# MCU.net
KiCad netlist of a schematic drawn in Altium Designer
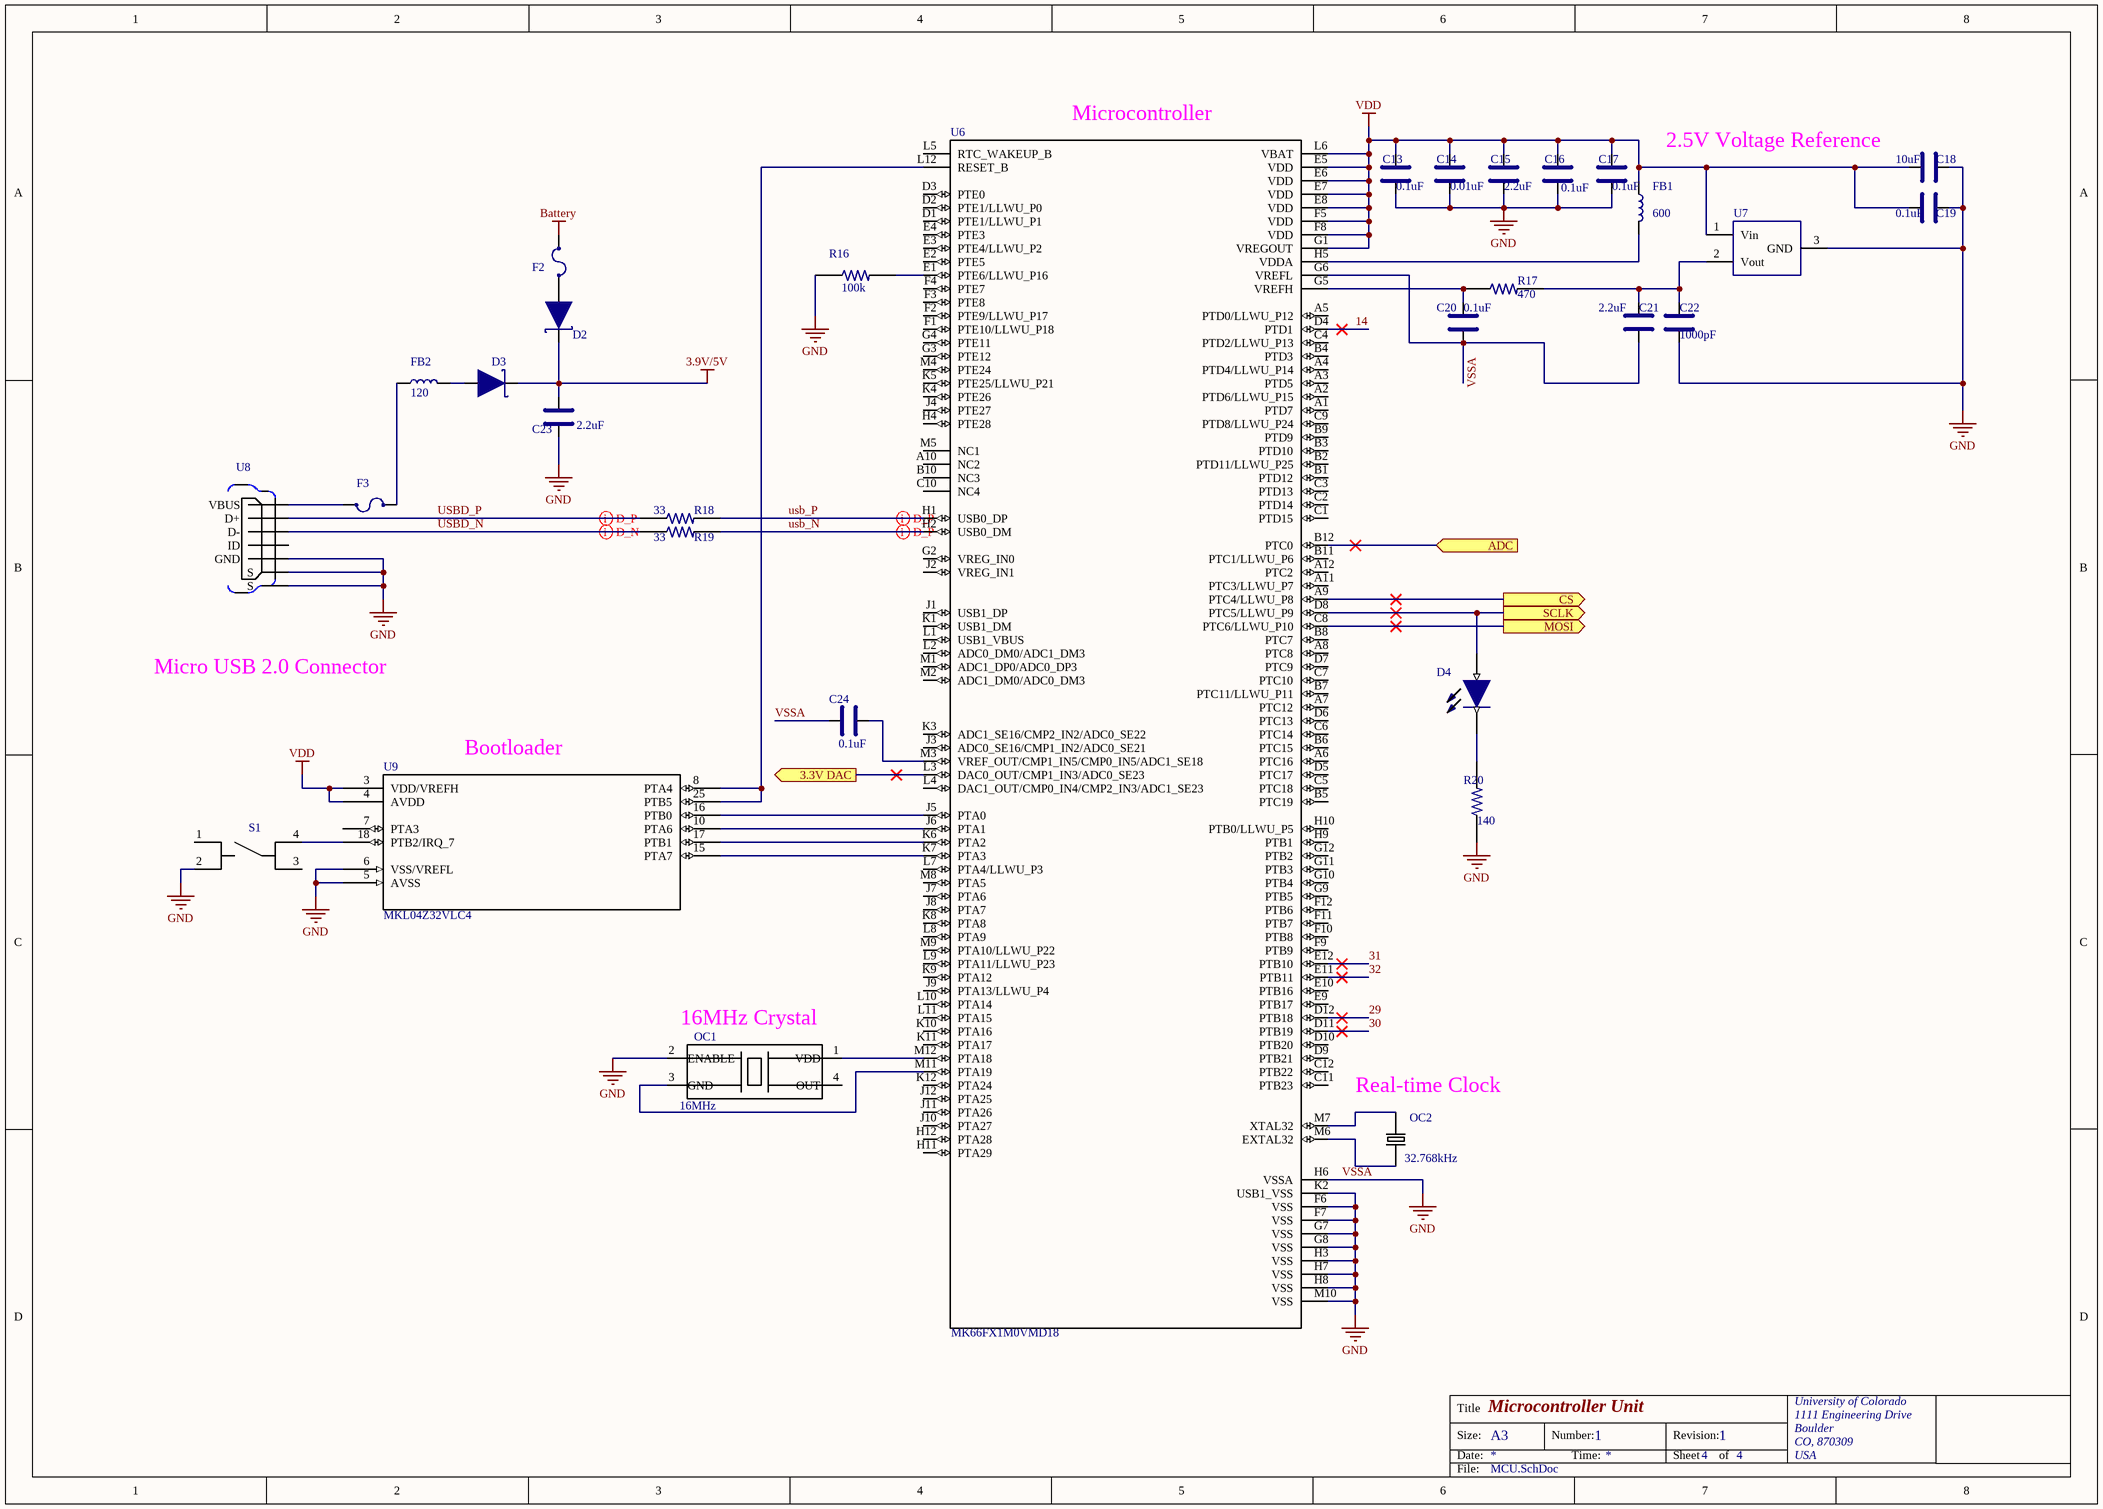
[diagram p0: MCU.SchDoc]

(export (version "E")
  (design (tool "Eeschema 10.0.6"))
  (components
    (comp (ref "C13")
      (value "0.1uF")
      (footprint "CL03A104KA3NNNC")
      (description "CAP CER 0.1UF 25V X5R 0201")
      (fields
        (field (name "MANUFACTURER") "Samsung")
        (field (name "MANUFACTURER PART NUMBER") "CL03A104KA3NNNC")
      )
      (libsource (lib "Sensing PEANO_Library") (part "CL03A104KA3NNNC"))
    )
    (comp (ref "C14")
      (value "0.01uF")
      (footprint "CL03B103KP3NNNC")
      (description "CAP CER 10000PF 10V X7R 0201")
      (fields
        (field (name "MANUFACTURER") "Samsung")
        (field (name "MANUFACTURER PART NUMBER") "CL03B103KP3NNNC")
      )
      (libsource (lib "Sensing PEANO_Library") (part "CL03B103KP3NNNC"))
    )
    (comp (ref "C15")
      (value "2.2uF")
      (footprint "CL03A225MP3CRNC")
      (description "CAP CER 2.2UF 10V X5R 0201")
      (fields
        (field (name "MANUFACTURER") "Samsung")
        (field (name "MANUFACTURER PART NUMBER") "CL03A225MP3CRNC")
      )
      (libsource (lib "Sensing PEANO_Library") (part "CL03A225MP3CRNC"))
    )
    (comp (ref "C16")
      (value "0.1uF")
      (footprint "CL03A104KA3NNNC")
      (description "CAP CER 0.1UF 25V X5R 0201")
      (fields
        (field (name "MANUFACTURER") "Samsung")
        (field (name "MANUFACTURER PART NUMBER") "CL03A104KA3NNNC")
      )
      (libsource (lib "Control_Board_Library") (part "CL03A104KA3NNNC"))
    )
    (comp (ref "C17")
      (value "0.1uF")
      (footprint "CL03A104KA3NNNC")
      (description "CAP CER 0.1UF 25V X5R 0201")
      (fields
        (field (name "MANUFACTURER") "Samsung")
        (field (name "MANUFACTURER PART NUMBER") "CL03A104KA3NNNC")
      )
      (libsource (lib "Sensing PEANO_Library") (part "CL03A104KA3NNNC"))
    )
    (comp (ref "C18")
      (value "10uF")
      (footprint "GRM155R60J106ME47D")
      (description "CAP CER 10UF 6.3V X5R 0402")
      (fields
        (field (name "MANUFACTURER") "Murata")
        (field (name "MANUFACTURER PART NUMBER") "GRM155R60J106ME47D")
      )
      (libsource (lib "Sensing PEANO_Library") (part "GRM155R60J106ME47D"))
    )
    (comp (ref "C19")
      (value "0.1uF")
      (footprint "CL03A104KA3NNNC")
      (description "CAP CER 0.1UF 25V X5R 0201")
      (fields
        (field (name "MANUFACTURER") "Samsung")
        (field (name "MANUFACTURER PART NUMBER") "CL03A104KA3NNNC")
      )
      (libsource (lib "Sensing PEANO_Library") (part "CL03A104KA3NNNC"))
    )
    (comp (ref "C20")
      (value "0.1uF")
      (footprint "CL03A104KA3NNNC")
      (description "CAP CER 0.1UF 25V X5R 0201")
      (fields
        (field (name "MANUFACTURER") "Samsung")
        (field (name "MANUFACTURER PART NUMBER") "CL03A104KA3NNNC")
      )
      (libsource (lib "Sensing PEANO_Library") (part "CL03A104KA3NNNC"))
    )
    (comp (ref "C21")
      (value "2.2uF")
      (footprint "CL03A225MP3CRNC")
      (description "CAP CER 2.2UF 10V X5R 0201")
      (fields
        (field (name "MANUFACTURER") "Samsung")
        (field (name "MANUFACTURER PART NUMBER") "CL03A225MP3CRNC")
      )
      (libsource (lib "Sensing PEANO_Library") (part "CL03A225MP3CRNC"))
    )
    (comp (ref "C22")
      (value "1000pF")
      (footprint "C0402C102K9RACTU")
      (description "CAP CER 1000PF 6.3V X7R 0402")
      (fields
        (field (name "MANUFACTURER") "Murata")
        (field (name "MANUFACTURER PART NUMBER") "GRM155R60J106ME47D")
      )
      (libsource (lib "Sensing PEANO_Library") (part "C0402C102K9RACTU"))
    )
    (comp (ref "C23")
      (value "2.2uF")
      (footprint "CL03A225MP3CRNC")
      (description "CAP CER 2.2UF 10V X5R 0201")
      (fields
        (field (name "MANUFACTURER") "Samsung")
        (field (name "MANUFACTURER PART NUMBER") "CL03A225MP3CRNC")
      )
      (libsource (lib "Sensing PEANO_Library") (part "CL03A225MP3CRNC"))
    )
    (comp (ref "C24")
      (value "0.1uF")
      (footprint "CL03A104KA3NNNC")
      (description "CAP CER 0.1UF 25V X5R 0201")
      (fields
        (field (name "MANUFACTURER") "Samsung")
        (field (name "MANUFACTURER PART NUMBER") "CL03A104KA3NNNC")
      )
      (libsource (lib "Sensing PEANO_Library") (part "CL03A104KA3NNNC"))
    )
    (comp (ref "D2")
      (value "LSM115JE3/TR13")
      (footprint "LSM115JE3/TR13")
      (description "DIODE SCHOTTKY 15V 1A DO214AC")
      (fields
        (field (name "MANUFACTURER") "Microsemi")
        (field (name "DIGIKEY PART NUMBER") "LSM115JE3/TR13CT-ND")
      )
      (libsource (lib "Sensing PEANO_Library") (part "LSM115JE3/TR13"))
    )
    (comp (ref "D3")
      (value "LSM115JE3/TR13")
      (footprint "LSM115JE3/TR13")
      (description "DIODE SCHOTTKY 15V 1A DO214AC")
      (fields
        (field (name "MANUFACTURER") "Microsemi")
        (field (name "DIGIKEY PART NUMBER") "LSM115JE3/TR13CT-ND")
      )
      (libsource (lib "Sensing PEANO_Library") (part "LSM115JE3/TR13"))
    )
    (comp (ref "D4")
      (value "SML-LXFM0603SUGCTR")
      (footprint "SML-LXFM0603SUGCTR")
      (description "LED GREEN CLEAR SMD")
      (fields
        (field (name "MANUFACTURER") "Lumex Opto/Components Inc.")
        (field (name "DIGIKEY PART NUMBER") "67-2320-1-ND")
      )
      (libsource (lib "Control_Board_Library") (part "SML-LXFM0603SUGCTR"))
    )
    (comp (ref "F2")
      (value "ERB-SD0R50U")
      (footprint "ERB-SD0R50U")
      (description "FUSE BOARD MNT 500MA 24VDC 0402")
      (fields (field (name "MANUFACTURER") "Panasonic") (field (name "DIGIKEY PART NUMBER") "P11361CT-ND"))
      (libsource (lib "Sensing PEANO_Library") (part "ERB-SD0R50U"))
    )
    (comp (ref "F3")
      (value "ERB-SD0R50U")
      (footprint "ERB-SD0R50U")
      (description "FUSE BOARD MNT 500MA 24VDC 0402")
      (fields (field (name "MANUFACTURER") "Panasonic") (field (name "DIGIKEY PART NUMBER") "P11361CT-ND"))
      (libsource (lib "Sensing PEANO_Library") (part "ERB-SD0R50U"))
    )
    (comp (ref "FB1")
      (value "600")
      (footprint "BLM15PX601SN1D")
      (description "FERRITE BEAD 600 OHM 0402 1LN")
      (fields
        (field (name "MANUFACTURER") "Murata")
        (field (name "MANUFACTURER PART NUMBER") "BLM15PX601SN1D")
      )
      (libsource (lib "Sensing PEANO_Library") (part "BLM15PX601SN1D"))
    )
    (comp (ref "FB2")
      (value "120")
      (footprint "MPZ0603S121HT000")
      (description "CHIP BEADS FOR GENERAL SIGNAL LI")
      (fields
        (field (name "MANUFACTURER") "TDK")
        (field (name "MANUFACTURER PART NUMBER") "MPZ0603S121HT000")
      )
      (libsource (lib "Sensing PEANO_Library") (part "MPZ0603S121HT000"))
    )
    (comp (ref "OC1")
      (value "16MHz")
      (footprint "TSX-3225 16.0000MF18X-AC3")
      (description "CRYSTAL 16.0000MHZ 9PF SMD")
      (fields
        (field (name "MANUFACTURER") "EPSON")
        (field (name "MANUFACTURER PART NUMBER") "TSX-3225 16.0000MF18X-AC3")
      )
      (libsource (lib "Control_Board_Library") (part "TSX-3225 16.0000MF18X-AC3"))
    )
    (comp (ref "OC2")
      (value "32.768kHz")
      (footprint "ECS-.327-9-34QS-TR")
      (description "CRYSTAL 32.768KHZ 9PF SMD")
      (fields
        (field (name "MANUFACTURER") "ECS")
        (field (name "MANUFACTURER PART NUMBER") "ECS-.327-9-34QS-TR")
      )
      (libsource (lib "Sensing PEANO_Library") (part "ECS-.327-9-34QS-TR"))
    )
    (comp (ref "R16")
      (value "100k")
      (footprint "RC0201FR-07100KL")
      (description "RES SMD 100K OHM 1% 1/20W 0201")
      (fields
        (field (name "MANUFACTURER") "Yageo")
        (field (name "MANUFACTURER PART NUMBER") "RC0201FR-07100KL")
      )
      (libsource (lib "Sensing PEANO_Library") (part "RC0201FR-07100KL"))
    )
    (comp (ref "R17")
      (value "470")
      (footprint "RC0201JR-07470RL")
      (description "RES SMD 470 OHM 5% 1/20W 0201")
      (fields
        (field (name "MANUFACTURER") "Yageo")
        (field (name "MANUFACTURER PART NUMBER") "RC0201JR-07470RL")
      )
      (libsource (lib "Sensing PEANO_Library") (part "RC0201JR-07470RL"))
    )
    (comp (ref "R18")
      (value "33")
      (footprint "RC0201JR-0733RL")
      (description "RES SMD 33 OHM 5% 1/20W 0201")
      (fields
        (field (name "MANUFACTURER") "Yageo")
        (field (name "MANUFACTURER PART NUMBER") "RC0201JR-0733RL")
      )
      (libsource (lib "Sensing PEANO_Library") (part "RC0201JR-0733RL"))
    )
    (comp (ref "R19")
      (value "33")
      (footprint "RC0201JR-0733RL")
      (description "RES SMD 33 OHM 5% 1/20W 0201")
      (fields
        (field (name "MANUFACTURER") "Yageo")
        (field (name "MANUFACTURER PART NUMBER") "RC0201JR-0733RL")
      )
      (libsource (lib "Sensing PEANO_Library") (part "RC0201JR-0733RL"))
    )
    (comp (ref "R20")
      (value "140")
      (footprint "RC0201FR-07140RL")
      (description "RES SMD 140 OHM 1% 1/20W 0201")
      (fields
        (field (name "MANUFACTURER") "Yageo")
        (field (name "MANUFACTURER PART NUMBER") "RC0201JR-0768RL")
      )
      (libsource (lib "Sensing PEANO_Library") (part "RC0201FR-07140RL"))
    )
    (comp (ref "S1")
      (value "KMR231NG LFS")
      (footprint "KMR221GLFS")
      (description "SWITCH TACTILE SPST-NO 0.02A 15V")
      (fields (field (name "MANUFACTURER") "C&K") (field (name "DIGIKEY PART NUMBER") "CKN10246TR-ND"))
      (libsource (lib "Control_Board_Library") (part "KMR231NG LFS"))
    )
    (comp (ref "U6")
      (value "MK66FX1M0VMD18")
      (footprint "MK66FX1M0VMD18")
      (description "Kinetis K66: 180MHz Cortex-M4F MCU, 1.2MB Flash, 256KB SRAM, 2xUSB, Ethernet, 144-MAPBGA")
      (fields
        (field (name "DIGIKEY PART NUMBER") "568-13335-ND")
        (field (name "MANUFACTURER") "NXP Semiconductors")
      )
      (libsource (lib "Sensing PEANO_Library") (part "MK66FX1M0VMD18"))
    )
    (comp (ref "U7")
      (value "ISL60002BIH325Z-T7A")
      (footprint "ISL60002-25")
      (description "IC VREF SERIES 2.5V SOT23-3")
      (fields
        (field (name "MANUFACTURER") "Renesas Electronics")
        (field (name "MANUFACTURER PART NUMBER") "ISL60002BIH325Z-TK")
      )
      (libsource (lib "Control_Board_Library") (part "ISL60002BIH325Z-T7A"))
    )
    (comp (ref "U8")
      (value "10118192-0001LF")
      (footprint "10118192-0001LF")
      (description "CONN USB MICRO B RECPT SMT R/A")
      (fields
        (field (name "MANUFACTURER") "Amphenol FCL")
        (field (name "DIGIKEY PART NUMBER") "609-4613-1-ND")
      )
      (libsource (lib "Control_Board_Library") (part "10118192-0001LF"))
    )
    (comp (ref "U9")
      (value "MKL04Z32VLC4")
      (footprint "MKL04Z32VLC4-ND")
      (description "IC MCU 32BIT 32KB FLASH 32LQFP")
      (fields
        (field (name "DIGIKEY PART NUMBER") "MKL04Z32VLC4-ND")
        (field (name "MANUFACTURER") "NXP Semiconductors")
      )
      (libsource (lib "Control_Board_Library") (part "MKL04Z32VLC4"))
    )
  )
  (nets
    (net (code "1") (name "/3.3V DAC") (class "Default")
      (node (ref "U6") (pin "L3") (pinfunction "DAC0_OUT/CMP1_IN3/ADC0_SE23_L3") (pintype "bidirectional"))
    )
    (net (code "2") (name "/14") (class "Default")
      (node (ref "U6") (pin "D4") (pinfunction "PTD1_D4") (pintype "bidirectional"))
    )
    (net (code "3") (name "/29") (class "Default")
      (node (ref "U6") (pin "D12") (pinfunction "PTB18_D12") (pintype "bidirectional"))
    )
    (net (code "4") (name "/30") (class "Default")
      (node (ref "U6") (pin "D11") (pinfunction "PTB19_D11") (pintype "bidirectional"))
    )
    (net (code "5") (name "/31") (class "Default")
      (node (ref "U6") (pin "E12") (pinfunction "PTB10_E12") (pintype "bidirectional"))
    )
    (net (code "6") (name "/32") (class "Default")
      (node (ref "U6") (pin "E11") (pinfunction "PTB11_E11") (pintype "bidirectional"))
    )
    (net (code "7") (name "/ADC") (class "Default")
      (node (ref "U6") (pin "B12") (pinfunction "PTC0_B12") (pintype "bidirectional"))
    )
    (net (code "8") (name "/CS") (class "Default")
      (node (ref "U6") (pin "A9") (pinfunction "PTC4/LLWU_P8_A9") (pintype "bidirectional"))
    )
    (net (code "9") (name "/MOSI") (class "Default")
      (node (ref "U6") (pin "C8") (pinfunction "PTC6/LLWU_P10_C8") (pintype "bidirectional"))
    )
    (net (code "10") (name "/SCLK") (class "Default")
      (node (ref "D4") (pin "1") (pinfunction "A_1") (pintype "input"))
      (node (ref "U6") (pin "D8") (pinfunction "PTC5/LLWU_P9_D8") (pintype "bidirectional"))
    )
    (net (code "11") (name "/USBD_N") (class "Default")
      (node (ref "R19") (pin "2") (pinfunction "2_2") (pintype "passive"))
      (node (ref "U8") (pin "2") (pinfunction "D-_2") (pintype "passive"))
    )
    (net (code "12") (name "/USBD_P") (class "Default")
      (node (ref "R18") (pin "2") (pinfunction "2_2") (pintype "passive"))
      (node (ref "U8") (pin "3") (pinfunction "D+_3") (pintype "passive"))
    )
    (net (code "13") (name "/usb_N") (class "Default")
      (node (ref "R19") (pin "1") (pinfunction "1_1") (pintype "passive"))
      (node (ref "U6") (pin "H2") (pinfunction "USB0_DM_H2") (pintype "bidirectional"))
    )
    (net (code "14") (name "/usb_P") (class "Default")
      (node (ref "R18") (pin "1") (pinfunction "1_1") (pintype "passive"))
      (node (ref "U6") (pin "H1") (pinfunction "USB0_DP_H1") (pintype "bidirectional"))
    )
    (net (code "15") (name "3.9V{slash}5V") (class "Default")
      (node (ref "C23") (pin "1") (pinfunction "1_1") (pintype "passive"))
      (node (ref "D2") (pin "1") (pinfunction "1_1") (pintype "passive"))
      (node (ref "D3") (pin "1") (pinfunction "1_1") (pintype "passive"))
    )
    (net (code "16") (name "Battery") (class "Default")
      (node (ref "F2") (pin "1") (pinfunction "In_1") (pintype "passive"))
    )
    (net (code "17") (name "GND") (class "Default")
      (node (ref "C13") (pin "2") (pinfunction "2_2") (pintype "passive"))
      (node (ref "C14") (pin "2") (pinfunction "2_2") (pintype "passive"))
      (node (ref "C15") (pin "2") (pinfunction "2_2") (pintype "passive"))
      (node (ref "C16") (pin "2") (pinfunction "2_2") (pintype "passive"))
      (node (ref "C17") (pin "2") (pinfunction "2_2") (pintype "passive"))
      (node (ref "C18") (pin "1") (pinfunction "1_1") (pintype "passive"))
      (node (ref "C19") (pin "2") (pinfunction "2_2") (pintype "passive"))
      (node (ref "C20") (pin "2") (pinfunction "2_2") (pintype "passive"))
      (node (ref "C21") (pin "1") (pinfunction "1_1") (pintype "passive"))
      (node (ref "C22") (pin "2") (pinfunction "2_2") (pintype "passive"))
      (node (ref "C23") (pin "2") (pinfunction "2_2") (pintype "passive"))
      (node (ref "C24") (pin "1") (pinfunction "1_1") (pintype "passive"))
      (node (ref "OC1") (pin "2") (pinfunction "ENABLE_2") (pintype "bidirectional"))
      (node (ref "R16") (pin "2") (pinfunction "2_2") (pintype "passive"))
      (node (ref "R20") (pin "2") (pinfunction "2_2") (pintype "passive"))
      (node (ref "S1") (pin "2") (pinfunction "2_2") (pintype "passive"))
      (node (ref "U6") (pin "F6") (pinfunction "VSS_F6") (pintype "passive"))
      (node (ref "U6") (pin "F7") (pinfunction "VSS_F7") (pintype "passive"))
      (node (ref "U6") (pin "G6") (pinfunction "VREFL_G6") (pintype "passive"))
      (node (ref "U6") (pin "G7") (pinfunction "VSS_G7") (pintype "passive"))
      (node (ref "U6") (pin "G8") (pinfunction "VSS_G8") (pintype "passive"))
      (node (ref "U6") (pin "H3") (pinfunction "VSS_H3") (pintype "passive"))
      (node (ref "U6") (pin "H6") (pinfunction "VSSA_H6") (pintype "passive"))
      (node (ref "U6") (pin "H7") (pinfunction "VSS_H7") (pintype "passive"))
      (node (ref "U6") (pin "H8") (pinfunction "VSS_H8") (pintype "passive"))
      (node (ref "U6") (pin "K2") (pinfunction "USB1_VSS_K2") (pintype "passive"))
      (node (ref "U6") (pin "M10") (pinfunction "VSS_M10") (pintype "passive"))
      (node (ref "U7") (pin "3") (pinfunction "GND_3") (pintype "passive"))
      (node (ref "U8") (pin "5") (pinfunction "GND_5") (pintype "passive"))
      (node (ref "U8") (pin "6") (pinfunction "S_6") (pintype "passive"))
      (node (ref "U8") (pin "7") (pinfunction "S_7") (pintype "passive"))
      (node (ref "U9") (pin "5") (pinfunction "AVSS_5") (pintype "input"))
      (node (ref "U9") (pin "6") (pinfunction "VSS/VREFL_6") (pintype "input"))
    )
    (net (code "18") (name "Net-(D3-Pad2)") (class "Default")
      (node (ref "D3") (pin "2") (pinfunction "2_2") (pintype "passive"))
      (node (ref "FB2") (pin "2") (pinfunction "2_2") (pintype "passive"))
    )
    (net (code "19") (name "Net-(D4-K)") (class "Default")
      (node (ref "D4") (pin "2") (pinfunction "K_2") (pintype "output"))
      (node (ref "R20") (pin "1") (pinfunction "1_1") (pintype "passive"))
    )
    (net (code "20") (name "Net-(F2-Out)") (class "Default")
      (node (ref "D2") (pin "2") (pinfunction "2_2") (pintype "passive"))
      (node (ref "F2") (pin "2") (pinfunction "Out_2") (pintype "passive"))
    )
    (net (code "21") (name "Net-(F3-In)") (class "Default")
      (node (ref "F3") (pin "1") (pinfunction "In_1") (pintype "passive"))
      (node (ref "FB2") (pin "1") (pinfunction "1_1") (pintype "passive"))
    )
    (net (code "22") (name "Net-(F3-Out)") (class "Default")
      (node (ref "F3") (pin "2") (pinfunction "Out_2") (pintype "passive"))
      (node (ref "U8") (pin "1") (pinfunction "VBUS_1") (pintype "passive"))
    )
    (net (code "23") (name "Net-(OC1-GND)") (class "Default")
      (node (ref "OC1") (pin "3") (pinfunction "GND_3") (pintype "bidirectional"))
      (node (ref "U6") (pin "M11") (pinfunction "PTA19_M11") (pintype "bidirectional"))
    )
    (net (code "24") (name "Net-(OC1-VDD)") (class "Default")
      (node (ref "OC1") (pin "1") (pinfunction "VDD_1") (pintype "bidirectional"))
      (node (ref "U6") (pin "M12") (pinfunction "PTA18_M12") (pintype "bidirectional"))
    )
    (net (code "25") (name "Net-(OC2-I{slash}O)") (class "Default")
      (node (ref "OC2") (pin "1") (pinfunction "I/O_1") (pintype "passive"))
      (node (ref "U6") (pin "M6") (pinfunction "EXTAL32_M6") (pintype "bidirectional"))
    )
    (net (code "26") (name "Net-(OC2-O{slash}I)") (class "Default")
      (node (ref "OC2") (pin "2") (pinfunction "O/I_2") (pintype "passive"))
      (node (ref "U6") (pin "M7") (pinfunction "XTAL32_M7") (pintype "bidirectional"))
    )
    (net (code "27") (name "Net-(U6-PTA0)") (class "Default")
      (node (ref "U6") (pin "J5") (pinfunction "PTA0_J5") (pintype "bidirectional"))
      (node (ref "U9") (pin "16") (pinfunction "PTB0_16") (pintype "bidirectional"))
    )
    (net (code "28") (name "Net-(U6-PTA1)") (class "Default")
      (node (ref "U6") (pin "J6") (pinfunction "PTA1_J6") (pintype "bidirectional"))
      (node (ref "U9") (pin "10") (pinfunction "PTA6_10") (pintype "bidirectional"))
    )
    (net (code "29") (name "Net-(U6-PTA2)") (class "Default")
      (node (ref "U6") (pin "K6") (pinfunction "PTA2_K6") (pintype "bidirectional"))
      (node (ref "U9") (pin "17") (pinfunction "PTB1_17") (pintype "bidirectional"))
    )
    (net (code "30") (name "Net-(U6-PTA3)") (class "Default")
      (node (ref "U6") (pin "K7") (pinfunction "PTA3_K7") (pintype "bidirectional"))
      (node (ref "U9") (pin "15") (pinfunction "PTA7_15") (pintype "bidirectional"))
    )
    (net (code "31") (name "Net-(U6-PTE6{slash}LLWU_P16)") (class "Default")
      (node (ref "R16") (pin "1") (pinfunction "1_1") (pintype "passive"))
      (node (ref "U6") (pin "E1") (pinfunction "PTE6/LLWU_P16_E1") (pintype "bidirectional"))
    )
    (net (code "32") (name "Net-(U6-RESET_B)") (class "Default")
      (node (ref "U6") (pin "L12") (pinfunction "RESET_B_L12") (pintype "passive"))
      (node (ref "U9") (pin "25") (pinfunction "PTB5_25") (pintype "bidirectional"))
      (node (ref "U9") (pin "8") (pinfunction "PTA4_8") (pintype "bidirectional"))
    )
    (net (code "33") (name "Net-(U6-VDDA)") (class "Default")
      (node (ref "FB1") (pin "2") (pinfunction "2_2") (pintype "passive"))
      (node (ref "U6") (pin "H5") (pinfunction "VDDA_H5") (pintype "passive"))
    )
    (net (code "34") (name "Net-(U6-VREFH)") (class "Default")
      (node (ref "C20") (pin "1") (pinfunction "1_1") (pintype "passive"))
      (node (ref "R17") (pin "2") (pinfunction "2_2") (pintype "passive"))
      (node (ref "U6") (pin "G5") (pinfunction "VREFH_G5") (pintype "passive"))
    )
    (net (code "35") (name "Net-(U6-VREF_OUT{slash}CMP1_IN5{slash}CMP0_IN5{slash}ADC1_SE18)") (class "Default")
      (node (ref "C24") (pin "2") (pinfunction "2_2") (pintype "passive"))
      (node (ref "U6") (pin "M3") (pinfunction "VREF_OUT/CMP1_IN5/CMP0_IN5/ADC1_SE18_M3") (pintype "bidirectional"))
    )
    (net (code "36") (name "Net-(U7-Vout)") (class "Default")
      (node (ref "C21") (pin "2") (pinfunction "2_2") (pintype "passive"))
      (node (ref "C22") (pin "1") (pinfunction "1_1") (pintype "passive"))
      (node (ref "R17") (pin "1") (pinfunction "1_1") (pintype "passive"))
      (node (ref "U7") (pin "2") (pinfunction "Vout_2") (pintype "passive"))
    )
    (net (code "37") (name "Net-(U9-PTB2{slash}IRQ_7)") (class "Default")
      (node (ref "S1") (pin "4") (pinfunction "4_4") (pintype "passive"))
      (node (ref "U9") (pin "18") (pinfunction "PTB2/IRQ_7_18") (pintype "bidirectional"))
    )
    (net (code "38") (name "VDD") (class "Default")
      (node (ref "C13") (pin "1") (pinfunction "1_1") (pintype "passive"))
      (node (ref "C14") (pin "1") (pinfunction "1_1") (pintype "passive"))
      (node (ref "C15") (pin "1") (pinfunction "1_1") (pintype "passive"))
      (node (ref "C16") (pin "1") (pinfunction "1_1") (pintype "passive"))
      (node (ref "C17") (pin "1") (pinfunction "1_1") (pintype "passive"))
      (node (ref "C18") (pin "2") (pinfunction "2_2") (pintype "passive"))
      (node (ref "C19") (pin "1") (pinfunction "1_1") (pintype "passive"))
      (node (ref "FB1") (pin "1") (pinfunction "1_1") (pintype "passive"))
      (node (ref "U6") (pin "E5") (pinfunction "VDD_E5") (pintype "passive"))
      (node (ref "U6") (pin "E6") (pinfunction "VDD_E6") (pintype "passive"))
      (node (ref "U6") (pin "E7") (pinfunction "VDD_E7") (pintype "passive"))
      (node (ref "U6") (pin "E8") (pinfunction "VDD_E8") (pintype "passive"))
      (node (ref "U6") (pin "F5") (pinfunction "VDD_F5") (pintype "passive"))
      (node (ref "U6") (pin "F8") (pinfunction "VDD_F8") (pintype "passive"))
      (node (ref "U6") (pin "G1") (pinfunction "VREGOUT_G1") (pintype "passive"))
      (node (ref "U6") (pin "L6") (pinfunction "VBAT_L6") (pintype "passive"))
      (node (ref "U7") (pin "1") (pinfunction "Vin_1") (pintype "passive"))
      (node (ref "U9") (pin "3") (pinfunction "VDD/VREFH_3") (pintype "power_in"))
      (node (ref "U9") (pin "4") (pinfunction "AVDD_4") (pintype "power_in"))
    )
    (net (code "39") (name "unconnected-(OC1-OUT-Pad4)") (class "Default")
      (node (ref "OC1") (pin "4") (pinfunction "OUT_4") (pintype "bidirectional"))
    )
    (net (code "40") (name "unconnected-(S1-Pad1)") (class "Default")
      (node (ref "S1") (pin "1") (pinfunction "1_1") (pintype "passive"))
    )
    (net (code "41") (name "unconnected-(S1-Pad3)") (class "Default")
      (node (ref "S1") (pin "3") (pinfunction "3_3") (pintype "passive"))
    )
    (net (code "42") (name "unconnected-(U6-ADC0_DM0{slash}ADC1_DM3-PadL2)") (class "Default")
      (node (ref "U6") (pin "L2") (pinfunction "ADC0_DM0/ADC1_DM3_L2") (pintype "bidirectional"))
    )
    (net (code "43") (name "unconnected-(U6-ADC0_SE16{slash}CMP1_IN2{slash}ADC0_SE21-PadJ3)") (class "Default")
      (node (ref "U6") (pin "J3") (pinfunction "ADC0_SE16/CMP1_IN2/ADC0_SE21_J3") (pintype "bidirectional"))
    )
    (net (code "44") (name "unconnected-(U6-ADC1_DM0{slash}ADC0_DM3-PadM2)") (class "Default")
      (node (ref "U6") (pin "M2") (pinfunction "ADC1_DM0/ADC0_DM3_M2") (pintype "bidirectional"))
    )
    (net (code "45") (name "unconnected-(U6-ADC1_DP0{slash}ADC0_DP3-PadM1)") (class "Default")
      (node (ref "U6") (pin "M1") (pinfunction "ADC1_DP0/ADC0_DP3_M1") (pintype "bidirectional"))
    )
    (net (code "46") (name "unconnected-(U6-ADC1_SE16{slash}CMP2_IN2{slash}ADC0_SE22-PadK3)") (class "Default")
      (node (ref "U6") (pin "K3") (pinfunction "ADC1_SE16/CMP2_IN2/ADC0_SE22_K3") (pintype "bidirectional"))
    )
    (net (code "47") (name "unconnected-(U6-DAC1_OUT{slash}CMP0_IN4{slash}CMP2_IN3{slash}ADC1_SE23-PadL4)") (class "Default")
      (node (ref "U6") (pin "L4") (pinfunction "DAC1_OUT/CMP0_IN4/CMP2_IN3/ADC1_SE23_L4") (pintype "bidirectional"))
    )
    (net (code "48") (name "unconnected-(U6-NC1-PadM5)") (class "Default")
      (node (ref "U6") (pin "M5") (pinfunction "NC1_M5") (pintype "passive"))
    )
    (net (code "49") (name "unconnected-(U6-NC2-PadA10)") (class "Default")
      (node (ref "U6") (pin "A10") (pinfunction "NC2_A10") (pintype "passive"))
    )
    (net (code "50") (name "unconnected-(U6-NC3-PadB10)") (class "Default")
      (node (ref "U6") (pin "B10") (pinfunction "NC3_B10") (pintype "passive"))
    )
    (net (code "51") (name "unconnected-(U6-NC4-PadC10)") (class "Default")
      (node (ref "U6") (pin "C10") (pinfunction "NC4_C10") (pintype "passive"))
    )
    (net (code "52") (name "unconnected-(U6-PTA4{slash}LLWU_P3-PadL7)") (class "Default")
      (node (ref "U6") (pin "L7") (pinfunction "PTA4/LLWU_P3_L7") (pintype "bidirectional"))
    )
    (net (code "53") (name "unconnected-(U6-PTA5-PadM8)") (class "Default")
      (node (ref "U6") (pin "M8") (pinfunction "PTA5_M8") (pintype "bidirectional"))
    )
    (net (code "54") (name "unconnected-(U6-PTA6-PadJ7)") (class "Default")
      (node (ref "U6") (pin "J7") (pinfunction "PTA6_J7") (pintype "bidirectional"))
    )
    (net (code "55") (name "unconnected-(U6-PTA7-PadJ8)") (class "Default")
      (node (ref "U6") (pin "J8") (pinfunction "PTA7_J8") (pintype "bidirectional"))
    )
    (net (code "56") (name "unconnected-(U6-PTA8-PadK8)") (class "Default")
      (node (ref "U6") (pin "K8") (pinfunction "PTA8_K8") (pintype "bidirectional"))
    )
    (net (code "57") (name "unconnected-(U6-PTA9-PadL8)") (class "Default")
      (node (ref "U6") (pin "L8") (pinfunction "PTA9_L8") (pintype "bidirectional"))
    )
    (net (code "58") (name "unconnected-(U6-PTA10{slash}LLWU_P22-PadM9)") (class "Default")
      (node (ref "U6") (pin "M9") (pinfunction "PTA10/LLWU_P22_M9") (pintype "bidirectional"))
    )
    (net (code "59") (name "unconnected-(U6-PTA11{slash}LLWU_P23-PadL9)") (class "Default")
      (node (ref "U6") (pin "L9") (pinfunction "PTA11/LLWU_P23_L9") (pintype "bidirectional"))
    )
    (net (code "60") (name "unconnected-(U6-PTA12-PadK9)") (class "Default")
      (node (ref "U6") (pin "K9") (pinfunction "PTA12_K9") (pintype "bidirectional"))
    )
    (net (code "61") (name "unconnected-(U6-PTA13{slash}LLWU_P4-PadJ9)") (class "Default")
      (node (ref "U6") (pin "J9") (pinfunction "PTA13/LLWU_P4_J9") (pintype "bidirectional"))
    )
    (net (code "62") (name "unconnected-(U6-PTA14-PadL10)") (class "Default")
      (node (ref "U6") (pin "L10") (pinfunction "PTA14_L10") (pintype "bidirectional"))
    )
    (net (code "63") (name "unconnected-(U6-PTA15-PadL11)") (class "Default")
      (node (ref "U6") (pin "L11") (pinfunction "PTA15_L11") (pintype "bidirectional"))
    )
    (net (code "64") (name "unconnected-(U6-PTA16-PadK10)") (class "Default")
      (node (ref "U6") (pin "K10") (pinfunction "PTA16_K10") (pintype "bidirectional"))
    )
    (net (code "65") (name "unconnected-(U6-PTA17-PadK11)") (class "Default")
      (node (ref "U6") (pin "K11") (pinfunction "PTA17_K11") (pintype "bidirectional"))
    )
    (net (code "66") (name "unconnected-(U6-PTA24-PadK12)") (class "Default")
      (node (ref "U6") (pin "K12") (pinfunction "PTA24_K12") (pintype "bidirectional"))
    )
    (net (code "67") (name "unconnected-(U6-PTA25-PadJ12)") (class "Default")
      (node (ref "U6") (pin "J12") (pinfunction "PTA25_J12") (pintype "bidirectional"))
    )
    (net (code "68") (name "unconnected-(U6-PTA26-PadJ11)") (class "Default")
      (node (ref "U6") (pin "J11") (pinfunction "PTA26_J11") (pintype "bidirectional"))
    )
    (net (code "69") (name "unconnected-(U6-PTA27-PadJ10)") (class "Default")
      (node (ref "U6") (pin "J10") (pinfunction "PTA27_J10") (pintype "bidirectional"))
    )
    (net (code "70") (name "unconnected-(U6-PTA28-PadH12)") (class "Default")
      (node (ref "U6") (pin "H12") (pinfunction "PTA28_H12") (pintype "bidirectional"))
    )
    (net (code "71") (name "unconnected-(U6-PTA29-PadH11)") (class "Default")
      (node (ref "U6") (pin "H11") (pinfunction "PTA29_H11") (pintype "bidirectional"))
    )
    (net (code "72") (name "unconnected-(U6-PTB0{slash}LLWU_P5-PadH10)") (class "Default")
      (node (ref "U6") (pin "H10") (pinfunction "PTB0/LLWU_P5_H10") (pintype "bidirectional"))
    )
    (net (code "73") (name "unconnected-(U6-PTB1-PadH9)") (class "Default")
      (node (ref "U6") (pin "H9") (pinfunction "PTB1_H9") (pintype "bidirectional"))
    )
    (net (code "74") (name "unconnected-(U6-PTB2-PadG12)") (class "Default")
      (node (ref "U6") (pin "G12") (pinfunction "PTB2_G12") (pintype "bidirectional"))
    )
    (net (code "75") (name "unconnected-(U6-PTB3-PadG11)") (class "Default")
      (node (ref "U6") (pin "G11") (pinfunction "PTB3_G11") (pintype "bidirectional"))
    )
    (net (code "76") (name "unconnected-(U6-PTB4-PadG10)") (class "Default")
      (node (ref "U6") (pin "G10") (pinfunction "PTB4_G10") (pintype "bidirectional"))
    )
    (net (code "77") (name "unconnected-(U6-PTB5-PadG9)") (class "Default")
      (node (ref "U6") (pin "G9") (pinfunction "PTB5_G9") (pintype "bidirectional"))
    )
    (net (code "78") (name "unconnected-(U6-PTB6-PadF12)") (class "Default")
      (node (ref "U6") (pin "F12") (pinfunction "PTB6_F12") (pintype "bidirectional"))
    )
    (net (code "79") (name "unconnected-(U6-PTB7-PadF11)") (class "Default")
      (node (ref "U6") (pin "F11") (pinfunction "PTB7_F11") (pintype "bidirectional"))
    )
    (net (code "80") (name "unconnected-(U6-PTB8-PadF10)") (class "Default")
      (node (ref "U6") (pin "F10") (pinfunction "PTB8_F10") (pintype "bidirectional"))
    )
    (net (code "81") (name "unconnected-(U6-PTB9-PadF9)") (class "Default")
      (node (ref "U6") (pin "F9") (pinfunction "PTB9_F9") (pintype "bidirectional"))
    )
    (net (code "82") (name "unconnected-(U6-PTB16-PadE10)") (class "Default")
      (node (ref "U6") (pin "E10") (pinfunction "PTB16_E10") (pintype "bidirectional"))
    )
    (net (code "83") (name "unconnected-(U6-PTB17-PadE9)") (class "Default")
      (node (ref "U6") (pin "E9") (pinfunction "PTB17_E9") (pintype "bidirectional"))
    )
    (net (code "84") (name "unconnected-(U6-PTB20-PadD10)") (class "Default")
      (node (ref "U6") (pin "D10") (pinfunction "PTB20_D10") (pintype "bidirectional"))
    )
    (net (code "85") (name "unconnected-(U6-PTB21-PadD9)") (class "Default")
      (node (ref "U6") (pin "D9") (pinfunction "PTB21_D9") (pintype "bidirectional"))
    )
    (net (code "86") (name "unconnected-(U6-PTB22-PadC12)") (class "Default")
      (node (ref "U6") (pin "C12") (pinfunction "PTB22_C12") (pintype "bidirectional"))
    )
    (net (code "87") (name "unconnected-(U6-PTB23-PadC11)") (class "Default")
      (node (ref "U6") (pin "C11") (pinfunction "PTB23_C11") (pintype "bidirectional"))
    )
    (net (code "88") (name "unconnected-(U6-PTC1{slash}LLWU_P6-PadB11)") (class "Default")
      (node (ref "U6") (pin "B11") (pinfunction "PTC1/LLWU_P6_B11") (pintype "bidirectional"))
    )
    (net (code "89") (name "unconnected-(U6-PTC2-PadA12)") (class "Default")
      (node (ref "U6") (pin "A12") (pinfunction "PTC2_A12") (pintype "bidirectional"))
    )
    (net (code "90") (name "unconnected-(U6-PTC3{slash}LLWU_P7-PadA11)") (class "Default")
      (node (ref "U6") (pin "A11") (pinfunction "PTC3/LLWU_P7_A11") (pintype "bidirectional"))
    )
    (net (code "91") (name "unconnected-(U6-PTC7-PadB8)") (class "Default")
      (node (ref "U6") (pin "B8") (pinfunction "PTC7_B8") (pintype "bidirectional"))
    )
    (net (code "92") (name "unconnected-(U6-PTC8-PadA8)") (class "Default")
      (node (ref "U6") (pin "A8") (pinfunction "PTC8_A8") (pintype "bidirectional"))
    )
    (net (code "93") (name "unconnected-(U6-PTC9-PadD7)") (class "Default")
      (node (ref "U6") (pin "D7") (pinfunction "PTC9_D7") (pintype "bidirectional"))
    )
    (net (code "94") (name "unconnected-(U6-PTC10-PadC7)") (class "Default")
      (node (ref "U6") (pin "C7") (pinfunction "PTC10_C7") (pintype "bidirectional"))
    )
    (net (code "95") (name "unconnected-(U6-PTC11{slash}LLWU_P11-PadB7)") (class "Default")
      (node (ref "U6") (pin "B7") (pinfunction "PTC11/LLWU_P11_B7") (pintype "bidirectional"))
    )
    (net (code "96") (name "unconnected-(U6-PTC12-PadA7)") (class "Default")
      (node (ref "U6") (pin "A7") (pinfunction "PTC12_A7") (pintype "bidirectional"))
    )
    (net (code "97") (name "unconnected-(U6-PTC13-PadD6)") (class "Default")
      (node (ref "U6") (pin "D6") (pinfunction "PTC13_D6") (pintype "bidirectional"))
    )
    (net (code "98") (name "unconnected-(U6-PTC14-PadC6)") (class "Default")
      (node (ref "U6") (pin "C6") (pinfunction "PTC14_C6") (pintype "bidirectional"))
    )
    (net (code "99") (name "unconnected-(U6-PTC15-PadB6)") (class "Default")
      (node (ref "U6") (pin "B6") (pinfunction "PTC15_B6") (pintype "bidirectional"))
    )
    (net (code "100") (name "unconnected-(U6-PTC16-PadA6)") (class "Default")
      (node (ref "U6") (pin "A6") (pinfunction "PTC16_A6") (pintype "bidirectional"))
    )
    (net (code "101") (name "unconnected-(U6-PTC17-PadD5)") (class "Default")
      (node (ref "U6") (pin "D5") (pinfunction "PTC17_D5") (pintype "bidirectional"))
    )
    (net (code "102") (name "unconnected-(U6-PTC18-PadC5)") (class "Default")
      (node (ref "U6") (pin "C5") (pinfunction "PTC18_C5") (pintype "bidirectional"))
    )
    (net (code "103") (name "unconnected-(U6-PTC19-PadB5)") (class "Default")
      (node (ref "U6") (pin "B5") (pinfunction "PTC19_B5") (pintype "bidirectional"))
    )
    (net (code "104") (name "unconnected-(U6-PTD0{slash}LLWU_P12-PadA5)") (class "Default")
      (node (ref "U6") (pin "A5") (pinfunction "PTD0/LLWU_P12_A5") (pintype "bidirectional"))
    )
    (net (code "105") (name "unconnected-(U6-PTD2{slash}LLWU_P13-PadC4)") (class "Default")
      (node (ref "U6") (pin "C4") (pinfunction "PTD2/LLWU_P13_C4") (pintype "bidirectional"))
    )
    (net (code "106") (name "unconnected-(U6-PTD3-PadB4)") (class "Default")
      (node (ref "U6") (pin "B4") (pinfunction "PTD3_B4") (pintype "bidirectional"))
    )
    (net (code "107") (name "unconnected-(U6-PTD4{slash}LLWU_P14-PadA4)") (class "Default")
      (node (ref "U6") (pin "A4") (pinfunction "PTD4/LLWU_P14_A4") (pintype "bidirectional"))
    )
    (net (code "108") (name "unconnected-(U6-PTD5-PadA3)") (class "Default")
      (node (ref "U6") (pin "A3") (pinfunction "PTD5_A3") (pintype "bidirectional"))
    )
    (net (code "109") (name "unconnected-(U6-PTD6{slash}LLWU_P15-PadA2)") (class "Default")
      (node (ref "U6") (pin "A2") (pinfunction "PTD6/LLWU_P15_A2") (pintype "bidirectional"))
    )
    (net (code "110") (name "unconnected-(U6-PTD7-PadA1)") (class "Default")
      (node (ref "U6") (pin "A1") (pinfunction "PTD7_A1") (pintype "bidirectional"))
    )
    (net (code "111") (name "unconnected-(U6-PTD8{slash}LLWU_P24-PadC9)") (class "Default")
      (node (ref "U6") (pin "C9") (pinfunction "PTD8/LLWU_P24_C9") (pintype "bidirectional"))
    )
    (net (code "112") (name "unconnected-(U6-PTD9-PadB9)") (class "Default")
      (node (ref "U6") (pin "B9") (pinfunction "PTD9_B9") (pintype "bidirectional"))
    )
    (net (code "113") (name "unconnected-(U6-PTD10-PadB3)") (class "Default")
      (node (ref "U6") (pin "B3") (pinfunction "PTD10_B3") (pintype "bidirectional"))
    )
    (net (code "114") (name "unconnected-(U6-PTD11{slash}LLWU_P25-PadB2)") (class "Default")
      (node (ref "U6") (pin "B2") (pinfunction "PTD11/LLWU_P25_B2") (pintype "bidirectional"))
    )
    (net (code "115") (name "unconnected-(U6-PTD12-PadB1)") (class "Default")
      (node (ref "U6") (pin "B1") (pinfunction "PTD12_B1") (pintype "bidirectional"))
    )
    (net (code "116") (name "unconnected-(U6-PTD13-PadC3)") (class "Default")
      (node (ref "U6") (pin "C3") (pinfunction "PTD13_C3") (pintype "bidirectional"))
    )
    (net (code "117") (name "unconnected-(U6-PTD14-PadC2)") (class "Default")
      (node (ref "U6") (pin "C2") (pinfunction "PTD14_C2") (pintype "bidirectional"))
    )
    (net (code "118") (name "unconnected-(U6-PTD15-PadC1)") (class "Default")
      (node (ref "U6") (pin "C1") (pinfunction "PTD15_C1") (pintype "bidirectional"))
    )
    (net (code "119") (name "unconnected-(U6-PTE0-PadD3)") (class "Default")
      (node (ref "U6") (pin "D3") (pinfunction "PTE0_D3") (pintype "bidirectional"))
    )
    (net (code "120") (name "unconnected-(U6-PTE1{slash}LLWU_P0-PadD2)") (class "Default")
      (node (ref "U6") (pin "D2") (pinfunction "PTE1/LLWU_P0_D2") (pintype "bidirectional"))
    )
    (net (code "121") (name "unconnected-(U6-PTE1{slash}LLWU_P1-PadD1)") (class "Default")
      (node (ref "U6") (pin "D1") (pinfunction "PTE1/LLWU_P1_D1") (pintype "bidirectional"))
    )
    (net (code "122") (name "unconnected-(U6-PTE3-PadE4)") (class "Default")
      (node (ref "U6") (pin "E4") (pinfunction "PTE3_E4") (pintype "bidirectional"))
    )
    (net (code "123") (name "unconnected-(U6-PTE4{slash}LLWU_P2-PadE3)") (class "Default")
      (node (ref "U6") (pin "E3") (pinfunction "PTE4/LLWU_P2_E3") (pintype "bidirectional"))
    )
    (net (code "124") (name "unconnected-(U6-PTE5-PadE2)") (class "Default")
      (node (ref "U6") (pin "E2") (pinfunction "PTE5_E2") (pintype "bidirectional"))
    )
    (net (code "125") (name "unconnected-(U6-PTE7-PadF4)") (class "Default")
      (node (ref "U6") (pin "F4") (pinfunction "PTE7_F4") (pintype "bidirectional"))
    )
    (net (code "126") (name "unconnected-(U6-PTE8-PadF3)") (class "Default")
      (node (ref "U6") (pin "F3") (pinfunction "PTE8_F3") (pintype "bidirectional"))
    )
    (net (code "127") (name "unconnected-(U6-PTE9{slash}LLWU_P17-PadF2)") (class "Default")
      (node (ref "U6") (pin "F2") (pinfunction "PTE9/LLWU_P17_F2") (pintype "bidirectional"))
    )
    (net (code "128") (name "unconnected-(U6-PTE10{slash}LLWU_P18-PadF1)") (class "Default")
      (node (ref "U6") (pin "F1") (pinfunction "PTE10/LLWU_P18_F1") (pintype "bidirectional"))
    )
    (net (code "129") (name "unconnected-(U6-PTE11-PadG4)") (class "Default")
      (node (ref "U6") (pin "G4") (pinfunction "PTE11_G4") (pintype "bidirectional"))
    )
    (net (code "130") (name "unconnected-(U6-PTE12-PadG3)") (class "Default")
      (node (ref "U6") (pin "G3") (pinfunction "PTE12_G3") (pintype "bidirectional"))
    )
    (net (code "131") (name "unconnected-(U6-PTE24-PadM4)") (class "Default")
      (node (ref "U6") (pin "M4") (pinfunction "PTE24_M4") (pintype "bidirectional"))
    )
    (net (code "132") (name "unconnected-(U6-PTE25{slash}LLWU_P21-PadK5)") (class "Default")
      (node (ref "U6") (pin "K5") (pinfunction "PTE25/LLWU_P21_K5") (pintype "bidirectional"))
    )
    (net (code "133") (name "unconnected-(U6-PTE26-PadK4)") (class "Default")
      (node (ref "U6") (pin "K4") (pinfunction "PTE26_K4") (pintype "bidirectional"))
    )
    (net (code "134") (name "unconnected-(U6-PTE27-PadJ4)") (class "Default")
      (node (ref "U6") (pin "J4") (pinfunction "PTE27_J4") (pintype "bidirectional"))
    )
    (net (code "135") (name "unconnected-(U6-PTE28-PadH4)") (class "Default")
      (node (ref "U6") (pin "H4") (pinfunction "PTE28_H4") (pintype "bidirectional"))
    )
    (net (code "136") (name "unconnected-(U6-RTC_WAKEUP_B-PadL5)") (class "Default")
      (node (ref "U6") (pin "L5") (pinfunction "RTC_WAKEUP_B_L5") (pintype "passive"))
    )
    (net (code "137") (name "unconnected-(U6-USB1_DM-PadK1)") (class "Default")
      (node (ref "U6") (pin "K1") (pinfunction "USB1_DM_K1") (pintype "bidirectional"))
    )
    (net (code "138") (name "unconnected-(U6-USB1_DP-PadJ1)") (class "Default")
      (node (ref "U6") (pin "J1") (pinfunction "USB1_DP_J1") (pintype "bidirectional"))
    )
    (net (code "139") (name "unconnected-(U6-USB1_VBUS-PadL1)") (class "Default")
      (node (ref "U6") (pin "L1") (pinfunction "USB1_VBUS_L1") (pintype "bidirectional"))
    )
    (net (code "140") (name "unconnected-(U6-VREG_IN0-PadG2)") (class "Default")
      (node (ref "U6") (pin "G2") (pinfunction "VREG_IN0_G2") (pintype "bidirectional"))
    )
    (net (code "141") (name "unconnected-(U6-VREG_IN1-PadJ2)") (class "Default")
      (node (ref "U6") (pin "J2") (pinfunction "VREG_IN1_J2") (pintype "bidirectional"))
    )
    (net (code "142") (name "unconnected-(U8-ID-Pad4)") (class "Default")
      (node (ref "U8") (pin "4") (pinfunction "ID_4") (pintype "passive"))
    )
    (net (code "143") (name "unconnected-(U9-PTA3-Pad7)") (class "Default")
      (node (ref "U9") (pin "7") (pinfunction "PTA3_7") (pintype "bidirectional"))
    )
  )
)
